# untitled.net
KiCad netlist of a schematic drawn in EAGLE
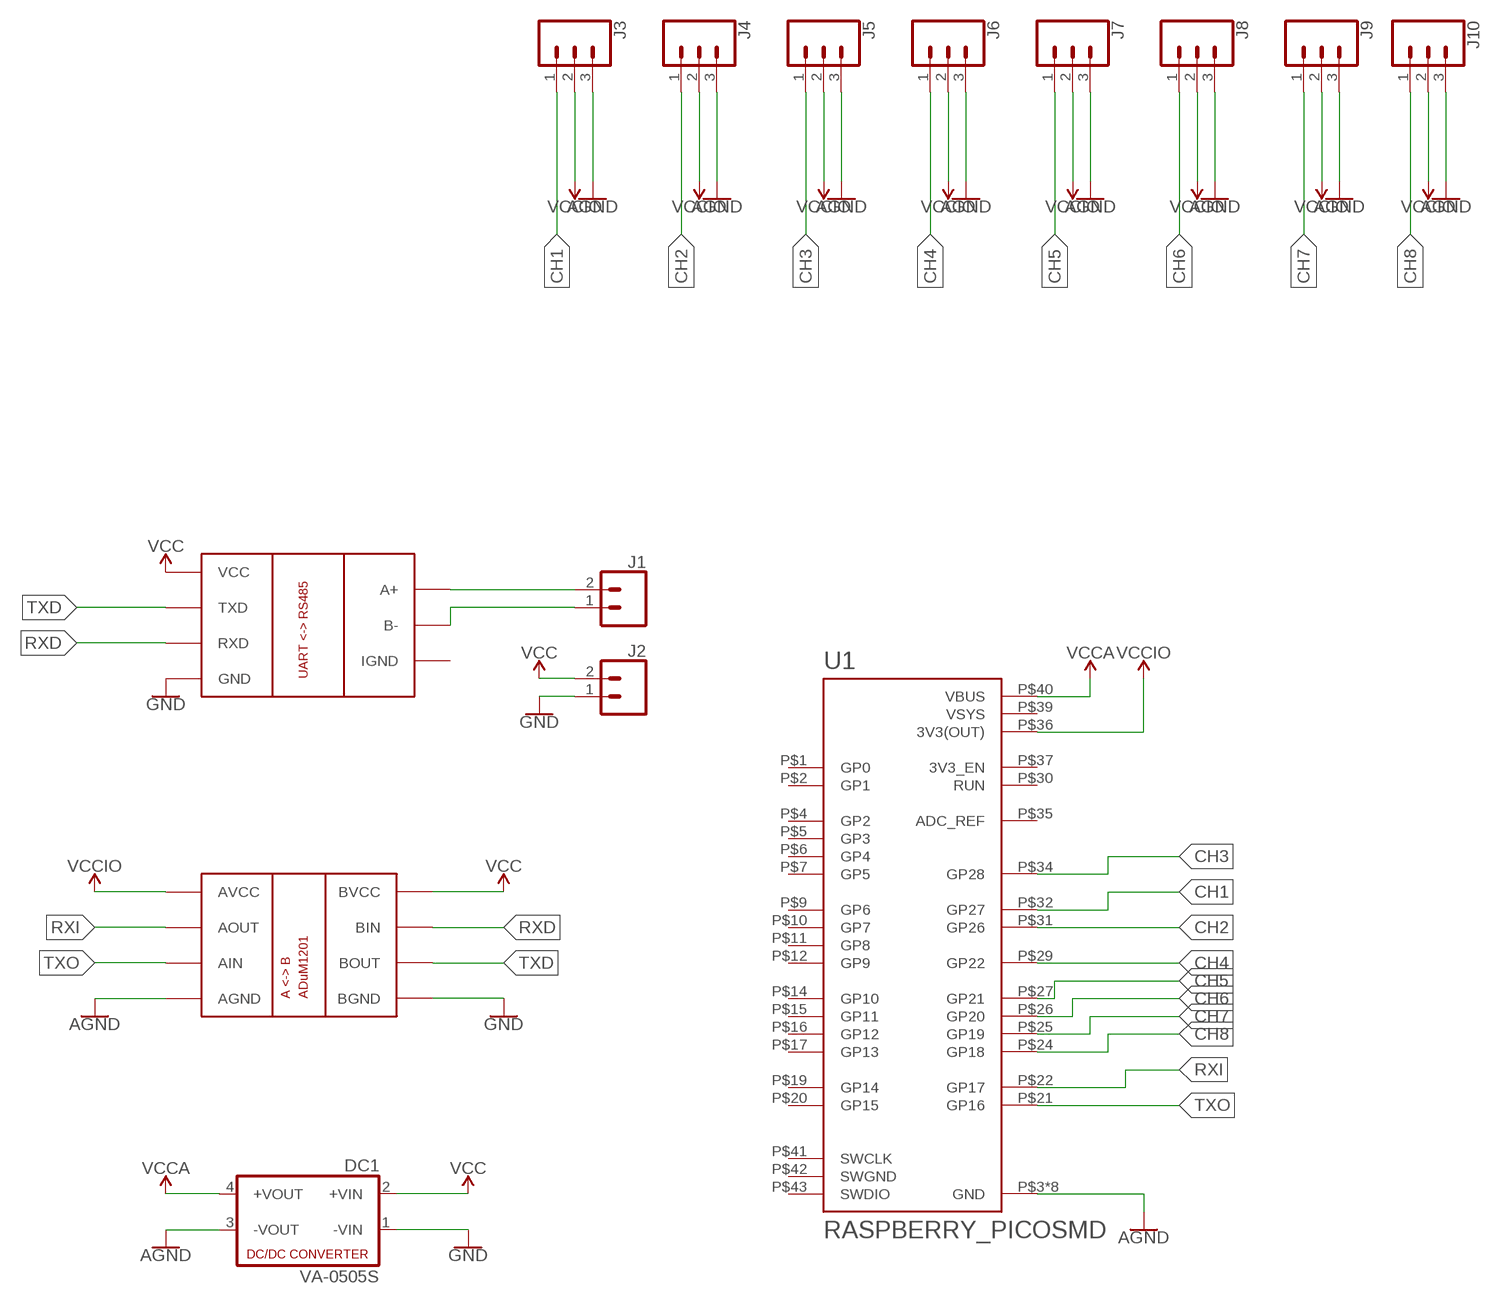
[diagram p0: schematic, sheet 1]

(export (version "E")
  (design (tool "Eeschema 10.0.6"))
  (components
    (comp (ref "DC1")
      (value "VA-0505S")
      (footprint "eagle-import:4SIL")
      (libsource (lib "eagle-import") (part "VA-?S0505"))
    )
    (comp (ref "J1")
      (value "CONN_025MM")
      (footprint "eagle-import:SCREWTERMINAL-5MM-2")
      (libsource (lib "eagle-import") (part "CONN_025MM"))
    )
    (comp (ref "J2")
      (value "CONN_025MM")
      (footprint "eagle-import:SCREWTERMINAL-5MM-2")
      (libsource (lib "eagle-import") (part "CONN_025MM"))
    )
    (comp (ref "J3")
      (value "CONN_03")
      (footprint "eagle-import:1X03")
      (libsource (lib "eagle-import") (part "CONN_03"))
    )
    (comp (ref "J4")
      (value "CONN_03")
      (footprint "eagle-import:1X03")
      (libsource (lib "eagle-import") (part "CONN_03"))
    )
    (comp (ref "J5")
      (value "CONN_03")
      (footprint "eagle-import:1X03")
      (libsource (lib "eagle-import") (part "CONN_03"))
    )
    (comp (ref "J6")
      (value "CONN_03")
      (footprint "eagle-import:1X03")
      (libsource (lib "eagle-import") (part "CONN_03"))
    )
    (comp (ref "J7")
      (value "CONN_03")
      (footprint "eagle-import:1X03")
      (libsource (lib "eagle-import") (part "CONN_03"))
    )
    (comp (ref "J8")
      (value "CONN_03")
      (footprint "eagle-import:1X03")
      (libsource (lib "eagle-import") (part "CONN_03"))
    )
    (comp (ref "J9")
      (value "CONN_03")
      (footprint "eagle-import:1X03")
      (libsource (lib "eagle-import") (part "CONN_03"))
    )
    (comp (ref "J10")
      (value "CONN_03")
      (footprint "eagle-import:1X03")
      (libsource (lib "eagle-import") (part "CONN_03"))
    )
    (comp (ref "U$1")
      (value "RS485-UART-CONVERTER")
      (footprint "eagle-import:RS485_MODULE")
      (libsource (lib "eagle-import") (part "RS485-UART-CONVERTER"))
    )
    (comp (ref "U$2")
      (value "ADUM1201")
      (footprint "eagle-import:SO8")
      (libsource (lib "eagle-import") (part "ADUM1201"))
    )
    (comp (ref "U1")
      (value "RASPBERRY_PICOSMD")
      (footprint "eagle-import:PICO-PKG-SMD")
      (libsource (lib "eagle-import") (part "RASPBERRY_PICOSMD"))
    )
  )
  (nets
    (net (code "1") (name "/SWGND") (class "Default")
      (node (ref "U1") (pin "P$42") (pinfunction "SWGND_P$42") (pintype "power_in"))
    )
    (net (code "2") (name "/VSYS") (class "Default")
      (node (ref "U1") (pin "P$39") (pinfunction "VSYS_P$39") (pintype "power_in"))
    )
    (net (code "3") (name "AGND") (class "Default")
      (node (ref "DC1") (pin "3") (pinfunction "-VOUT_3") (pintype "passive"))
      (node (ref "J10") (pin "3") (pinfunction "3_3") (pintype "passive"))
      (node (ref "J3") (pin "3") (pinfunction "3_3") (pintype "passive"))
      (node (ref "J4") (pin "3") (pinfunction "3_3") (pintype "passive"))
      (node (ref "J5") (pin "3") (pinfunction "3_3") (pintype "passive"))
      (node (ref "J6") (pin "3") (pinfunction "3_3") (pintype "passive"))
      (node (ref "J7") (pin "3") (pinfunction "3_3") (pintype "passive"))
      (node (ref "J8") (pin "3") (pinfunction "3_3") (pintype "passive"))
      (node (ref "J9") (pin "3") (pinfunction "3_3") (pintype "passive"))
      (node (ref "U$2") (pin "4") (pinfunction "AGND_4") (pintype "bidirectional"))
      (node (ref "U1") (pin "P$13") (pinfunction "GND_P$13") (pintype "power_in"))
      (node (ref "U1") (pin "P$18") (pinfunction "GND_P$18") (pintype "power_in"))
      (node (ref "U1") (pin "P$23") (pinfunction "GND_P$23") (pintype "power_in"))
      (node (ref "U1") (pin "P$28") (pinfunction "GND_P$28") (pintype "power_in"))
      (node (ref "U1") (pin "P$3") (pinfunction "GND_P$3") (pintype "power_in"))
      (node (ref "U1") (pin "P$33") (pinfunction "GND_P$33") (pintype "power_in"))
      (node (ref "U1") (pin "P$38") (pinfunction "GND_P$38") (pintype "power_in"))
      (node (ref "U1") (pin "P$8") (pinfunction "GND_P$8") (pintype "power_in"))
    )
    (net (code "4") (name "CH1") (class "Default")
      (node (ref "J3") (pin "1") (pinfunction "1_1") (pintype "passive"))
      (node (ref "U1") (pin "P$32") (pinfunction "GP27_P$32") (pintype "bidirectional"))
    )
    (net (code "5") (name "CH2") (class "Default")
      (node (ref "J4") (pin "1") (pinfunction "1_1") (pintype "passive"))
      (node (ref "U1") (pin "P$31") (pinfunction "GP26_P$31") (pintype "bidirectional"))
    )
    (net (code "6") (name "CH3") (class "Default")
      (node (ref "J5") (pin "1") (pinfunction "1_1") (pintype "passive"))
      (node (ref "U1") (pin "P$34") (pinfunction "GP28_P$34") (pintype "bidirectional"))
    )
    (net (code "7") (name "CH4") (class "Default")
      (node (ref "J6") (pin "1") (pinfunction "1_1") (pintype "passive"))
      (node (ref "U1") (pin "P$29") (pinfunction "GP22_P$29") (pintype "bidirectional"))
    )
    (net (code "8") (name "CH5") (class "Default")
      (node (ref "J7") (pin "1") (pinfunction "1_1") (pintype "passive"))
      (node (ref "U1") (pin "P$27") (pinfunction "GP21_P$27") (pintype "bidirectional"))
    )
    (net (code "9") (name "CH6") (class "Default")
      (node (ref "J8") (pin "1") (pinfunction "1_1") (pintype "passive"))
      (node (ref "U1") (pin "P$26") (pinfunction "GP20_P$26") (pintype "bidirectional"))
    )
    (net (code "10") (name "CH7") (class "Default")
      (node (ref "J9") (pin "1") (pinfunction "1_1") (pintype "passive"))
      (node (ref "U1") (pin "P$25") (pinfunction "GP19_P$25") (pintype "bidirectional"))
    )
    (net (code "11") (name "CH8") (class "Default")
      (node (ref "J10") (pin "1") (pinfunction "1_1") (pintype "passive"))
      (node (ref "U1") (pin "P$24") (pinfunction "GP18_P$24") (pintype "bidirectional"))
    )
    (net (code "12") (name "GND") (class "Default")
      (node (ref "DC1") (pin "1") (pinfunction "-VIN_1") (pintype "passive"))
      (node (ref "J2") (pin "1") (pinfunction "1_1") (pintype "passive"))
      (node (ref "U$1") (pin "GND") (pinfunction "GND_GND") (pintype "bidirectional"))
      (node (ref "U$2") (pin "5") (pinfunction "BGND_5") (pintype "bidirectional"))
    )
    (net (code "13") (name "Net-(J1-Pad1)") (class "Default")
      (node (ref "J1") (pin "1") (pinfunction "1_1") (pintype "passive"))
      (node (ref "U$1") (pin "B-") (pinfunction "B-_B-") (pintype "bidirectional"))
    )
    (net (code "14") (name "Net-(J1-Pad2)") (class "Default")
      (node (ref "J1") (pin "2") (pinfunction "2_2") (pintype "passive"))
      (node (ref "U$1") (pin "A+") (pinfunction "A+_A+") (pintype "bidirectional"))
    )
    (net (code "15") (name "RXD") (class "Default")
      (node (ref "U$1") (pin "RXD") (pinfunction "RXD_RXD") (pintype "bidirectional"))
      (node (ref "U$2") (pin "7") (pinfunction "BIN_7") (pintype "bidirectional"))
    )
    (net (code "16") (name "RXI") (class "Default")
      (node (ref "U$2") (pin "2") (pinfunction "AOUT_2") (pintype "bidirectional"))
      (node (ref "U1") (pin "P$22") (pinfunction "GP17_P$22") (pintype "bidirectional"))
    )
    (net (code "17") (name "TXD") (class "Default")
      (node (ref "U$1") (pin "TXD") (pinfunction "TXD_TXD") (pintype "bidirectional"))
      (node (ref "U$2") (pin "6") (pinfunction "BOUT_6") (pintype "bidirectional"))
    )
    (net (code "18") (name "TXO") (class "Default")
      (node (ref "U$2") (pin "3") (pinfunction "AIN_3") (pintype "bidirectional"))
      (node (ref "U1") (pin "P$21") (pinfunction "GP16_P$21") (pintype "bidirectional"))
    )
    (net (code "19") (name "VCC") (class "Default")
      (node (ref "DC1") (pin "2") (pinfunction "+VIN_2") (pintype "passive"))
      (node (ref "J2") (pin "2") (pinfunction "2_2") (pintype "passive"))
      (node (ref "U$1") (pin "VCC") (pinfunction "VCC_VCC") (pintype "bidirectional"))
      (node (ref "U$2") (pin "8") (pinfunction "BVCC_8") (pintype "bidirectional"))
    )
    (net (code "20") (name "VCCA") (class "Default")
      (node (ref "DC1") (pin "4") (pinfunction "+VOUT_4") (pintype "passive"))
      (node (ref "U1") (pin "P$40") (pinfunction "VBUS_P$40") (pintype "power_in"))
    )
    (net (code "21") (name "VCCIO") (class "Default")
      (node (ref "J10") (pin "2") (pinfunction "2_2") (pintype "passive"))
      (node (ref "J3") (pin "2") (pinfunction "2_2") (pintype "passive"))
      (node (ref "J4") (pin "2") (pinfunction "2_2") (pintype "passive"))
      (node (ref "J5") (pin "2") (pinfunction "2_2") (pintype "passive"))
      (node (ref "J6") (pin "2") (pinfunction "2_2") (pintype "passive"))
      (node (ref "J7") (pin "2") (pinfunction "2_2") (pintype "passive"))
      (node (ref "J8") (pin "2") (pinfunction "2_2") (pintype "passive"))
      (node (ref "J9") (pin "2") (pinfunction "2_2") (pintype "passive"))
      (node (ref "U$2") (pin "1") (pinfunction "AVCC_1") (pintype "bidirectional"))
      (node (ref "U1") (pin "P$36") (pinfunction "3V3(OUT)_P$36") (pintype "power_in"))
    )
    (net (code "22") (name "unconnected-(U$1-IGND-PadISOGND)") (class "Default")
      (node (ref "U$1") (pin "ISOGND") (pinfunction "IGND_ISOGND") (pintype "bidirectional"))
    )
    (net (code "23") (name "unconnected-(U1-3V3_EN-PadP$37)") (class "Default")
      (node (ref "U1") (pin "P$37") (pinfunction "3V3_EN_P$37") (pintype "input"))
    )
    (net (code "24") (name "unconnected-(U1-ADC_REF-PadP$35)") (class "Default")
      (node (ref "U1") (pin "P$35") (pinfunction "ADC_REF_P$35") (pintype "input"))
    )
    (net (code "25") (name "unconnected-(U1-GP0-PadP$1)") (class "Default")
      (node (ref "U1") (pin "P$1") (pinfunction "GP0_P$1") (pintype "bidirectional"))
    )
    (net (code "26") (name "unconnected-(U1-GP1-PadP$2)") (class "Default")
      (node (ref "U1") (pin "P$2") (pinfunction "GP1_P$2") (pintype "bidirectional"))
    )
    (net (code "27") (name "unconnected-(U1-GP2-PadP$4)") (class "Default")
      (node (ref "U1") (pin "P$4") (pinfunction "GP2_P$4") (pintype "bidirectional"))
    )
    (net (code "28") (name "unconnected-(U1-GP3-PadP$5)") (class "Default")
      (node (ref "U1") (pin "P$5") (pinfunction "GP3_P$5") (pintype "bidirectional"))
    )
    (net (code "29") (name "unconnected-(U1-GP4-PadP$6)") (class "Default")
      (node (ref "U1") (pin "P$6") (pinfunction "GP4_P$6") (pintype "bidirectional"))
    )
    (net (code "30") (name "unconnected-(U1-GP5-PadP$7)") (class "Default")
      (node (ref "U1") (pin "P$7") (pinfunction "GP5_P$7") (pintype "bidirectional"))
    )
    (net (code "31") (name "unconnected-(U1-GP6-PadP$9)") (class "Default")
      (node (ref "U1") (pin "P$9") (pinfunction "GP6_P$9") (pintype "bidirectional"))
    )
    (net (code "32") (name "unconnected-(U1-GP7-PadP$10)") (class "Default")
      (node (ref "U1") (pin "P$10") (pinfunction "GP7_P$10") (pintype "bidirectional"))
    )
    (net (code "33") (name "unconnected-(U1-GP8-PadP$11)") (class "Default")
      (node (ref "U1") (pin "P$11") (pinfunction "GP8_P$11") (pintype "bidirectional"))
    )
    (net (code "34") (name "unconnected-(U1-GP9-PadP$12)") (class "Default")
      (node (ref "U1") (pin "P$12") (pinfunction "GP9_P$12") (pintype "bidirectional"))
    )
    (net (code "35") (name "unconnected-(U1-GP10-PadP$14)") (class "Default")
      (node (ref "U1") (pin "P$14") (pinfunction "GP10_P$14") (pintype "bidirectional"))
    )
    (net (code "36") (name "unconnected-(U1-GP11-PadP$15)") (class "Default")
      (node (ref "U1") (pin "P$15") (pinfunction "GP11_P$15") (pintype "bidirectional"))
    )
    (net (code "37") (name "unconnected-(U1-GP12-PadP$16)") (class "Default")
      (node (ref "U1") (pin "P$16") (pinfunction "GP12_P$16") (pintype "bidirectional"))
    )
    (net (code "38") (name "unconnected-(U1-GP13-PadP$17)") (class "Default")
      (node (ref "U1") (pin "P$17") (pinfunction "GP13_P$17") (pintype "bidirectional"))
    )
    (net (code "39") (name "unconnected-(U1-GP14-PadP$19)") (class "Default")
      (node (ref "U1") (pin "P$19") (pinfunction "GP14_P$19") (pintype "bidirectional"))
    )
    (net (code "40") (name "unconnected-(U1-GP15-PadP$20)") (class "Default")
      (node (ref "U1") (pin "P$20") (pinfunction "GP15_P$20") (pintype "bidirectional"))
    )
    (net (code "41") (name "unconnected-(U1-RUN-PadP$30)") (class "Default")
      (node (ref "U1") (pin "P$30") (pinfunction "RUN_P$30") (pintype "input"))
    )
    (net (code "42") (name "unconnected-(U1-SWCLK-PadP$41)") (class "Default")
      (node (ref "U1") (pin "P$41") (pinfunction "SWCLK_P$41") (pintype "input"))
    )
    (net (code "43") (name "unconnected-(U1-SWDIO-PadP$43)") (class "Default")
      (node (ref "U1") (pin "P$43") (pinfunction "SWDIO_P$43") (pintype "bidirectional"))
    )
  )
)
